# relais_platine_v3.net
KiCad netlist of a schematic drawn in EAGLE
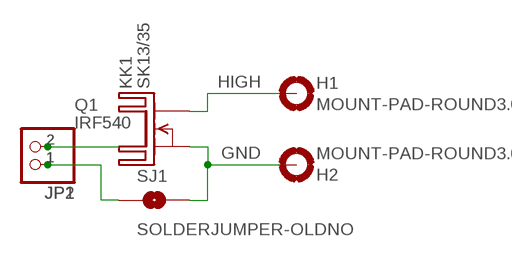
[diagram p0: schematic, sheet 1]

(export (version "E")
  (design (tool "Eeschema 10.0.6"))
  (components
    (comp (ref "H1")
      (value "MOUNT-PAD-ROUND3.0")
      (footprint "eagle-import:3,0-PAD")
      (libsource (lib "eagle-import") (part "MOUNT-PAD-ROUND3.0"))
    )
    (comp (ref "H2")
      (value "MOUNT-PAD-ROUND3.0")
      (footprint "eagle-import:3,0-PAD")
      (libsource (lib "eagle-import") (part "MOUNT-PAD-ROUND3.0"))
    )
    (comp (ref "JP1")
      (value "PINHD-1X2")
      (footprint "eagle-import:1X02")
      (libsource (lib "eagle-import") (part "PINHD-1X2"))
    )
    (comp (ref "JP2")
      (value "PINHD-1X2/90")
      (footprint "eagle-import:1X02_90")
      (libsource (lib "eagle-import") (part "PINHD-1X2/90"))
    )
    (comp (ref "KK1")
      (value "SK13/35")
      (footprint "eagle-import:SK13_35")
      (libsource (lib "eagle-import") (part "SK13/35"))
    )
    (comp (ref "Q1")
      (value "IRF540")
      (footprint "eagle-import:TO220")
      (libsource (lib "eagle-import") (part "IRF540"))
    )
    (comp (ref "SJ1")
      (value "SOLDERJUMPER-OLDNO")
      (footprint "eagle-import:SJ_2S-NO")
      (libsource (lib "eagle-import") (part "SOLDERJUMPER-OLDNO"))
    )
  )
  (nets
    (net (code "1") (name "/GND") (class "Default")
      (node (ref "H2") (pin "B3,0") (pinfunction "MOUNT_B3,0") (pintype "passive"))
      (node (ref "Q1") (pin "3") (pinfunction "S_3") (pintype "passive"))
      (node (ref "SJ1") (pin "2") (pinfunction "2_2") (pintype "passive"))
    )
    (net (code "2") (name "/HIGH") (class "Default")
      (node (ref "H1") (pin "B3,0") (pinfunction "MOUNT_B3,0") (pintype "passive"))
      (node (ref "Q1") (pin "2") (pinfunction "D_2") (pintype "passive"))
    )
    (net (code "3") (name "Net-(JP1-Pad1)") (class "Default")
      (node (ref "JP1") (pin "1") (pinfunction "1_1") (pintype "passive"))
      (node (ref "JP2") (pin "1") (pinfunction "1_1") (pintype "passive"))
      (node (ref "SJ1") (pin "1") (pinfunction "1_1") (pintype "passive"))
    )
    (net (code "4") (name "Net-(Q1-G)") (class "Default")
      (node (ref "JP1") (pin "2") (pinfunction "2_2") (pintype "passive"))
      (node (ref "JP2") (pin "2") (pinfunction "2_2") (pintype "passive"))
      (node (ref "Q1") (pin "1") (pinfunction "G_1") (pintype "passive"))
    )
  )
)
